# ANL_P54_Buffer.net
KiCad netlist of a schematic drawn in Altium Designer
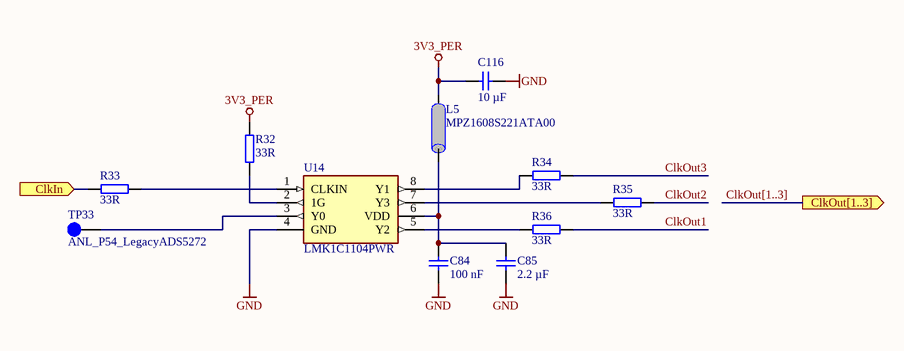
[diagram p0: ANL_P54_Buffer.SchDoc]

(export (version "E")
  (design (tool "Eeschema 10.0.6"))
  (components
    (comp (ref "C84")
      (value "100 nF")
      (footprint "C_0603_TE")
      (description "Generic capacitor")
      (fields
        (field (name "MANUFACTURER PART NUMBER") "UZgen_C_0603_100nF_50V_X7R")
        (field (name "MANUFACTURER") "UZgen")
        (field (name "CREATED FROM") "AGeiger")
      )
      (libsource (lib "user") (part "CAP-NP"))
    )
    (comp (ref "C85")
      (value "2.2 µF")
      (footprint "C_0603_TE")
      (description "Generic capacitor")
      (fields
        (field (name "MANUFACTURER PART NUMBER") "UZgen_C_0603_2.2uF_50V_X7R")
        (field (name "MANUFACTURER") "UZgen")
        (field (name "CREATED FROM") "UZgenTool")
      )
      (libsource (lib "user") (part "CAP-NP"))
    )
    (comp (ref "C116")
      (value "10 µF")
      (footprint "C_0603_TE")
      (description "Generic capacitor")
      (fields
        (field (name "MANUFACTURER PART NUMBER") "UZgen_C_0603_10uF_6.3V_X7R")
        (field (name "MANUFACTURER") "UZgen")
        (field (name "CREATED FROM") "UZgenTool")
      )
      (libsource (lib "user") (part "CAP-NP"))
    )
    (comp (ref "L5")
      (value "MPZ1608S221ATA00")
      (footprint "RES 0603_1608")
      (description "Ferritperle, 0603, 220 ohm, 2.2 A, Baureihe MPZ, 0.05 ohm, ± 25%")
      (fields
        (field (name "MANUFACTURER") "TDK")
        (field (name "LCSC PART NUMBER") "C76815")
        (field (name "CREATED FROM") "MGremer")
      )
      (libsource (lib "user") (part "Ferrite_Bead"))
    )
    (comp (ref "R32")
      (value "33R")
      (footprint "R_0603_TE")
      (description "Generic resistor")
      (fields
        (field (name "MANUFACTURER PART NUMBER") "UZgen_R_0603_33R")
        (field (name "MANUFACTURER") "UZgen")
        (field (name "CREATED FROM") "UZgenTool")
      )
      (libsource (lib "user") (part "RES"))
    )
    (comp (ref "R33")
      (value "33R")
      (footprint "R_0603_TE")
      (description "Generic resistor")
      (fields
        (field (name "MANUFACTURER PART NUMBER") "UZgen_R_0603_33R")
        (field (name "MANUFACTURER") "UZgen")
        (field (name "CREATED FROM") "UZgenTool")
      )
      (libsource (lib "user") (part "RES"))
    )
    (comp (ref "R34")
      (value "33R")
      (footprint "R_0603_TE")
      (description "Generic resistor")
      (fields
        (field (name "MANUFACTURER PART NUMBER") "UZgen_R_0603_33R")
        (field (name "MANUFACTURER") "UZgen")
        (field (name "CREATED FROM") "UZgenTool")
      )
      (libsource (lib "user") (part "RES"))
    )
    (comp (ref "R35")
      (value "33R")
      (footprint "R_0603_TE")
      (description "Generic resistor")
      (fields
        (field (name "MANUFACTURER PART NUMBER") "UZgen_R_0603_33R")
        (field (name "MANUFACTURER") "UZgen")
        (field (name "CREATED FROM") "UZgenTool")
      )
      (libsource (lib "user") (part "RES"))
    )
    (comp (ref "R36")
      (value "33R")
      (footprint "R_0603_TE")
      (description "Generic resistor")
      (fields
        (field (name "MANUFACTURER PART NUMBER") "UZgen_R_0603_33R")
        (field (name "MANUFACTURER") "UZgen")
        (field (name "CREATED FROM") "UZgenTool")
      )
      (libsource (lib "user") (part "RES"))
    )
    (comp (ref "TP33")
      (value "ANL_P54_LegacyADS5272")
      (footprint "TP_1mm")
      (description "Testpoint 1mm")
      (fields
        (field (name "MANUFACTURER PART NUMBER") "NULL")
        (field (name "CREATED") "2018_06_25_AGeiger")
        (field (name "CREATED FROM") "AGeiger")
      )
      (libsource (lib "user") (part "TP_1mm"))
    )
    (comp (ref "U14")
      (value "LMK1C1104PWR")
      (footprint "TSSOP-8")
      (description "250MHz TSSOP-8 Clock Buffers, Drivers ROHS")
      (fields
        (field (name "MANUFACTURER") "Texas Instruments")
        (field (name "LCSC PART NUMBER") "C1855734")
        (field (name "CREATED FROM") "FRosner")
      )
      (libsource (lib "user") (part "LMK1C1104PWR"))
    )
  )
  (nets
    (net (code "1") (name "/ClkIn") (class "Default")
      (node (ref "R33") (pin "2") (pinfunction "2_2") (pintype "passive"))
    )
    (net (code "2") (name "/ClkOut1") (class "Default")
      (node (ref "R36") (pin "1") (pinfunction "1_1") (pintype "passive"))
    )
    (net (code "3") (name "/ClkOut2") (class "Default")
      (node (ref "R35") (pin "1") (pinfunction "1_1") (pintype "passive"))
    )
    (net (code "4") (name "/ClkOut3") (class "Default")
      (node (ref "R34") (pin "1") (pinfunction "1_1") (pintype "passive"))
    )
    (net (code "6") (name "3V3_PER") (class "Default")
      (node (ref "C116") (pin "2") (pinfunction "2_2") (pintype "passive"))
      (node (ref "L5") (pin "1") (pinfunction "1_1") (pintype "passive"))
      (node (ref "R32") (pin "1") (pinfunction "1_1") (pintype "passive"))
    )
    (net (code "7") (name "GND") (class "Default")
      (node (ref "C116") (pin "1") (pinfunction "1_1") (pintype "passive"))
      (node (ref "C84") (pin "1") (pinfunction "1_1") (pintype "passive"))
      (node (ref "C85") (pin "1") (pinfunction "1_1") (pintype "passive"))
      (node (ref "U14") (pin "4") (pinfunction "GND_4") (pintype "power_in"))
    )
    (net (code "8") (name "Net-(U14-1G)") (class "Default")
      (node (ref "R32") (pin "2") (pinfunction "2_2") (pintype "passive"))
      (node (ref "U14") (pin "2") (pinfunction "1G_2") (pintype "output"))
    )
    (net (code "9") (name "Net-(U14-CLKIN)") (class "Default")
      (node (ref "R33") (pin "1") (pinfunction "1_1") (pintype "passive"))
      (node (ref "U14") (pin "1") (pinfunction "CLKIN_1") (pintype "input"))
    )
    (net (code "10") (name "Net-(U14-VDD)") (class "Default")
      (node (ref "C84") (pin "2") (pinfunction "2_2") (pintype "passive"))
      (node (ref "C85") (pin "2") (pinfunction "2_2") (pintype "passive"))
      (node (ref "L5") (pin "2") (pinfunction "2_2") (pintype "passive"))
      (node (ref "U14") (pin "6") (pinfunction "VDD_6") (pintype "power_in"))
    )
    (net (code "11") (name "Net-(U14-Y0)") (class "Default")
      (node (ref "TP33") (pin "1") (pintype "passive"))
      (node (ref "U14") (pin "3") (pinfunction "Y0_3") (pintype "output"))
    )
    (net (code "12") (name "Net-(U14-Y1)") (class "Default")
      (node (ref "R34") (pin "2") (pinfunction "2_2") (pintype "passive"))
      (node (ref "U14") (pin "8") (pinfunction "Y1_8") (pintype "output"))
    )
    (net (code "13") (name "Net-(U14-Y2)") (class "Default")
      (node (ref "R36") (pin "2") (pinfunction "2_2") (pintype "passive"))
      (node (ref "U14") (pin "5") (pinfunction "Y2_5") (pintype "output"))
    )
    (net (code "14") (name "Net-(U14-Y3)") (class "Default")
      (node (ref "R35") (pin "2") (pinfunction "2_2") (pintype "passive"))
      (node (ref "U14") (pin "7") (pinfunction "Y3_7") (pintype "output"))
    )
  )
)
